# FTDI-Breakout_v20.net
KiCad netlist of a schematic drawn in EAGLE
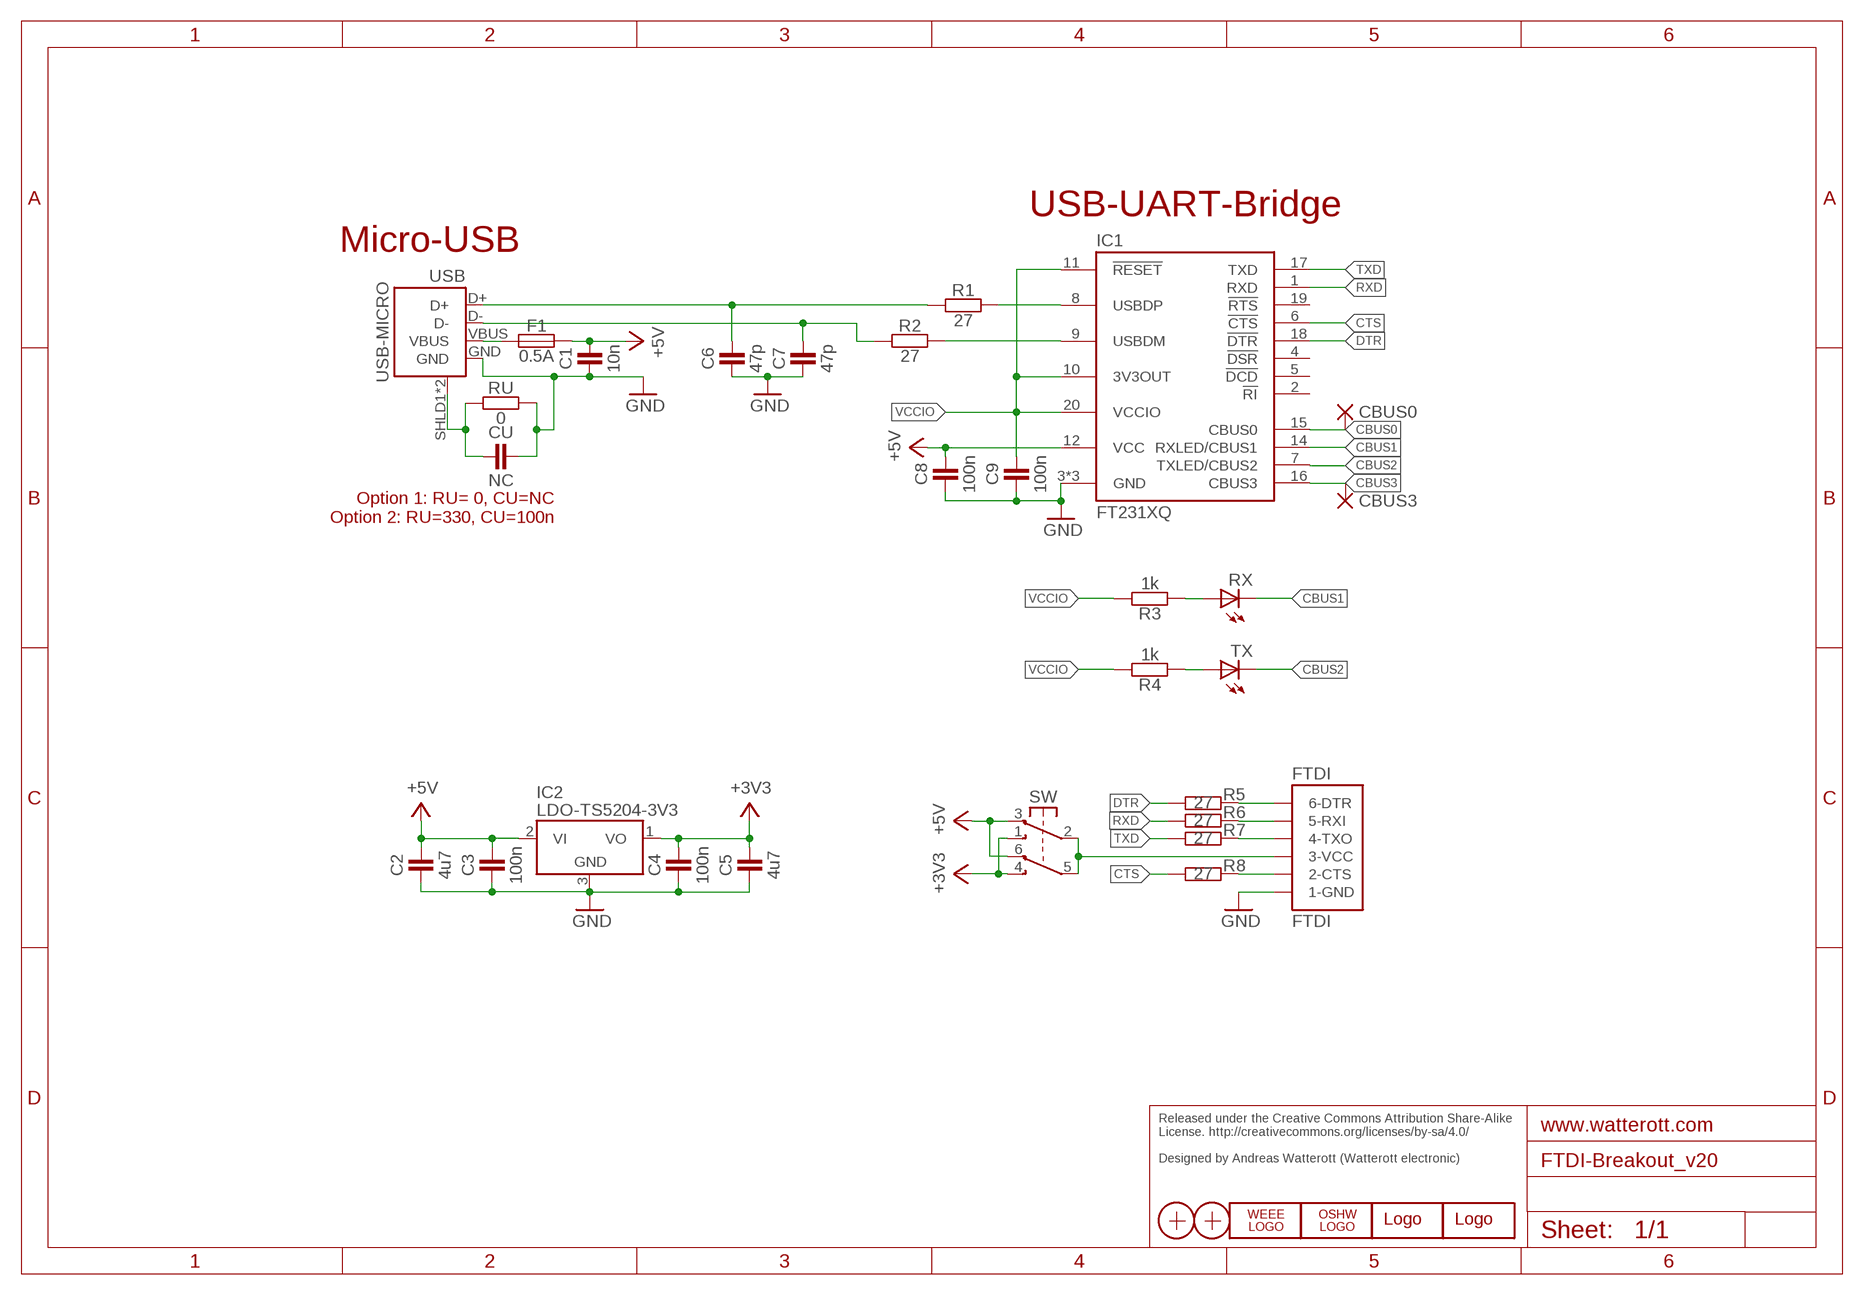
[diagram p0: schematic, sheet 1]

(export (version "E")
  (design (tool "Eeschema 10.0.6"))
  (components
    (comp (ref "C1")
      (value "10n")
      (footprint "eagle-import:C0603")
      (libsource (lib "eagle-import") (part "CAPACITOR-0603"))
    )
    (comp (ref "C2")
      (value "4u7")
      (footprint "eagle-import:C0805")
      (libsource (lib "eagle-import") (part "CAPACITOR-0805"))
    )
    (comp (ref "C3")
      (value "100n")
      (footprint "eagle-import:C0603")
      (libsource (lib "eagle-import") (part "CAPACITOR-0603"))
    )
    (comp (ref "C4")
      (value "100n")
      (footprint "eagle-import:C0603")
      (libsource (lib "eagle-import") (part "CAPACITOR-0603"))
    )
    (comp (ref "C5")
      (value "4u7")
      (footprint "eagle-import:C0805")
      (libsource (lib "eagle-import") (part "CAPACITOR-0805"))
    )
    (comp (ref "C6")
      (value "47p")
      (footprint "eagle-import:C0603")
      (libsource (lib "eagle-import") (part "CAPACITOR-0603"))
    )
    (comp (ref "C7")
      (value "47p")
      (footprint "eagle-import:C0603")
      (libsource (lib "eagle-import") (part "CAPACITOR-0603"))
    )
    (comp (ref "C8")
      (value "100n")
      (footprint "eagle-import:C0603")
      (libsource (lib "eagle-import") (part "CAPACITOR-0603"))
    )
    (comp (ref "C9")
      (value "100n")
      (footprint "eagle-import:C0603")
      (libsource (lib "eagle-import") (part "CAPACITOR-0603"))
    )
    (comp (ref "CBUS0")
      (value "PAD-1.27X1.27_NC")
      (footprint "eagle-import:PAD-1.27X1.27_NC")
      (libsource (lib "eagle-import") (part "PAD-1.27X1.27_NC"))
    )
    (comp (ref "CBUS3")
      (value "PAD-1.27X1.27_NC")
      (footprint "eagle-import:PAD-1.27X1.27_NC")
      (libsource (lib "eagle-import") (part "PAD-1.27X1.27_NC"))
    )
    (comp (ref "CU")
      (value "NC")
      (footprint "eagle-import:C0603")
      (libsource (lib "eagle-import") (part "CAPACITOR-0603"))
    )
    (comp (ref "F1")
      (value "0.5A")
      (footprint "eagle-import:C0805")
      (libsource (lib "eagle-import") (part "FUSE-0805"))
    )
    (comp (ref "FTDI")
      (value "FTDI")
      (footprint "eagle-import:FTDI")
      (libsource (lib "eagle-import") (part "FTDI"))
    )
    (comp (ref "IC1")
      (value "FT231XQ")
      (footprint "eagle-import:QFN20-PAD")
      (libsource (lib "eagle-import") (part "FT231XQ"))
    )
    (comp (ref "IC2")
      (value "LDO-TS5204-3V3")
      (footprint "eagle-import:SOT23")
      (libsource (lib "eagle-import") (part "LDO-TS5204-3V3"))
    )
    (comp (ref "LOGO1")
      (value "WEEE_LOGO-S")
      (footprint "eagle-import:WEEE_TPLAC_S")
      (libsource (lib "eagle-import") (part "WEEE_LOGO-S"))
    )
    (comp (ref "LOGO2")
      (value "OSHW_LOGOX0070")
      (footprint "eagle-import:OSHW_6X70")
      (libsource (lib "eagle-import") (part "OSHW_LOGOX0070"))
    )
    (comp (ref "LOGO3")
      (value "LOGO-S_PLACE_S")
      (footprint "eagle-import:SPARK_TPLACE_S")
      (libsource (lib "eagle-import") (part "LOGO-S_PLACE_S"))
    )
    (comp (ref "LOGO4")
      (value "LOGO-S_PLACE_M")
      (footprint "eagle-import:SPARK_TPLACE_M")
      (libsource (lib "eagle-import") (part "LOGO-S_PLACE_M"))
    )
    (comp (ref "R1")
      (value "27")
      (footprint "eagle-import:C0603")
      (libsource (lib "eagle-import") (part "RESISTOR-0603"))
    )
    (comp (ref "R2")
      (value "27")
      (footprint "eagle-import:C0603")
      (libsource (lib "eagle-import") (part "RESISTOR-0603"))
    )
    (comp (ref "R3")
      (value "1k")
      (footprint "eagle-import:C0603")
      (libsource (lib "eagle-import") (part "RESISTOR-0603"))
    )
    (comp (ref "R4")
      (value "1k")
      (footprint "eagle-import:C0603")
      (libsource (lib "eagle-import") (part "RESISTOR-0603"))
    )
    (comp (ref "R5")
      (value "27")
      (footprint "eagle-import:C0603")
      (libsource (lib "eagle-import") (part "RESISTOR-0603"))
    )
    (comp (ref "R6")
      (value "27")
      (footprint "eagle-import:C0603")
      (libsource (lib "eagle-import") (part "RESISTOR-0603"))
    )
    (comp (ref "R7")
      (value "27")
      (footprint "eagle-import:C0603")
      (libsource (lib "eagle-import") (part "RESISTOR-0603"))
    )
    (comp (ref "R8")
      (value "27")
      (footprint "eagle-import:C0603")
      (libsource (lib "eagle-import") (part "RESISTOR-0603"))
    )
    (comp (ref "RU")
      (value "0")
      (footprint "eagle-import:C0603")
      (libsource (lib "eagle-import") (part "RESISTOR-0603"))
    )
    (comp (ref "RX")
      (value "LED-0603")
      (footprint "eagle-import:C0603")
      (libsource (lib "eagle-import") (part "LED-0603"))
    )
    (comp (ref "SW")
      (value "SW-2UM-CUS22B")
      (footprint "eagle-import:SW_CUS22B")
      (libsource (lib "eagle-import") (part "SW-2UM-CUS22B"))
    )
    (comp (ref "TX")
      (value "LED-0603")
      (footprint "eagle-import:C0603")
      (libsource (lib "eagle-import") (part "LED-0603"))
    )
    (comp (ref "USB")
      (value "USB-MICRO")
      (footprint "eagle-import:USB-MICRO-10103594")
      (libsource (lib "eagle-import") (part "USB-MICRO"))
    )
    (comp (ref "X1")
      (value "PASSER-07")
      (footprint "eagle-import:PASSER_07MM")
      (libsource (lib "eagle-import") (part "PASSER-07"))
    )
    (comp (ref "X2")
      (value "PASSER-07")
      (footprint "eagle-import:PASSER_07MM")
      (libsource (lib "eagle-import") (part "PASSER-07"))
    )
  )
  (nets
    (net (code "1") (name "+3V3") (class "Default")
      (node (ref "C4") (pin "2") (pinfunction "2_2") (pintype "passive"))
      (node (ref "C5") (pin "2") (pinfunction "2_2") (pintype "passive"))
      (node (ref "IC2") (pin "1") (pinfunction "VO_1") (pintype "passive"))
      (node (ref "SW") (pin "1") (pinfunction "S1_1") (pintype "passive"))
      (node (ref "SW") (pin "4") (pinfunction "S2_4") (pintype "passive"))
    )
    (net (code "2") (name "+5V") (class "Default")
      (node (ref "C1") (pin "2") (pinfunction "2_2") (pintype "passive"))
      (node (ref "C2") (pin "2") (pinfunction "2_2") (pintype "passive"))
      (node (ref "C3") (pin "2") (pinfunction "2_2") (pintype "passive"))
      (node (ref "C8") (pin "2") (pinfunction "2_2") (pintype "passive"))
      (node (ref "F1") (pin "2") (pinfunction "2_2") (pintype "passive"))
      (node (ref "IC1") (pin "12") (pinfunction "VCC_12") (pintype "power_in"))
      (node (ref "IC2") (pin "2") (pinfunction "VI_2") (pintype "input"))
      (node (ref "SW") (pin "3") (pinfunction "O1_3") (pintype "passive"))
      (node (ref "SW") (pin "6") (pinfunction "O2_6") (pintype "passive"))
    )
    (net (code "3") (name "CBUS0") (class "Default")
      (node (ref "CBUS0") (pin "1") (pinfunction "P_1") (pintype "passive"))
      (node (ref "IC1") (pin "15") (pinfunction "CBUS0_15") (pintype "bidirectional"))
    )
    (net (code "4") (name "CBUS1") (class "Default")
      (node (ref "IC1") (pin "14") (pinfunction "RXLED/CBUS1_14") (pintype "bidirectional"))
      (node (ref "RX") (pin "C") (pinfunction "C_C") (pintype "passive"))
    )
    (net (code "5") (name "CBUS2") (class "Default")
      (node (ref "IC1") (pin "7") (pinfunction "TXLED/CBUS2_7") (pintype "bidirectional"))
      (node (ref "TX") (pin "C") (pinfunction "C_C") (pintype "passive"))
    )
    (net (code "6") (name "CBUS3") (class "Default")
      (node (ref "CBUS3") (pin "1") (pinfunction "P_1") (pintype "passive"))
      (node (ref "IC1") (pin "16") (pinfunction "CBUS3_16") (pintype "bidirectional"))
    )
    (net (code "7") (name "CTS") (class "Default")
      (node (ref "IC1") (pin "6") (pinfunction "~{CTS}_6") (pintype "bidirectional"))
      (node (ref "R8") (pin "1") (pinfunction "1_1") (pintype "passive"))
    )
    (net (code "8") (name "DTR") (class "Default")
      (node (ref "IC1") (pin "18") (pinfunction "~{DTR}_18") (pintype "bidirectional"))
      (node (ref "R5") (pin "1") (pinfunction "1_1") (pintype "passive"))
    )
    (net (code "9") (name "GND") (class "Default")
      (node (ref "C1") (pin "1") (pinfunction "1_1") (pintype "passive"))
      (node (ref "C2") (pin "1") (pinfunction "1_1") (pintype "passive"))
      (node (ref "C3") (pin "1") (pinfunction "1_1") (pintype "passive"))
      (node (ref "C4") (pin "1") (pinfunction "1_1") (pintype "passive"))
      (node (ref "C5") (pin "1") (pinfunction "1_1") (pintype "passive"))
      (node (ref "C6") (pin "1") (pinfunction "1_1") (pintype "passive"))
      (node (ref "C7") (pin "1") (pinfunction "1_1") (pintype "passive"))
      (node (ref "C8") (pin "1") (pinfunction "1_1") (pintype "passive"))
      (node (ref "C9") (pin "1") (pinfunction "1_1") (pintype "passive"))
      (node (ref "CU") (pin "2") (pinfunction "2_2") (pintype "passive"))
      (node (ref "FTDI") (pin "1-GND") (pinfunction "1-GND_1-GND") (pintype "power_in"))
      (node (ref "IC1") (pin "13") (pinfunction "GND_13") (pintype "power_in"))
      (node (ref "IC1") (pin "3") (pinfunction "GND_3") (pintype "power_in"))
      (node (ref "IC1") (pin "TP") (pinfunction "GND_TP") (pintype "power_in"))
      (node (ref "IC2") (pin "3") (pinfunction "GND_3") (pintype "passive"))
      (node (ref "RU") (pin "2") (pinfunction "2_2") (pintype "passive"))
      (node (ref "USB") (pin "GND") (pinfunction "GND_GND") (pintype "power_in"))
    )
    (net (code "10") (name "Net-(C6-Pad2)") (class "Default")
      (node (ref "C6") (pin "2") (pinfunction "2_2") (pintype "passive"))
      (node (ref "R1") (pin "1") (pinfunction "1_1") (pintype "passive"))
      (node (ref "USB") (pin "D+") (pinfunction "D+_D+") (pintype "bidirectional"))
    )
    (net (code "11") (name "Net-(C7-Pad2)") (class "Default")
      (node (ref "C7") (pin "2") (pinfunction "2_2") (pintype "passive"))
      (node (ref "R2") (pin "1") (pinfunction "1_1") (pintype "passive"))
      (node (ref "USB") (pin "D-") (pinfunction "D-_D-") (pintype "bidirectional"))
    )
    (net (code "12") (name "Net-(CU-Pad1)") (class "Default")
      (node (ref "CU") (pin "1") (pinfunction "1_1") (pintype "passive"))
      (node (ref "RU") (pin "1") (pinfunction "1_1") (pintype "passive"))
      (node (ref "USB") (pin "SHLD1") (pinfunction "SHIELD_SHLD1") (pintype "passive"))
      (node (ref "USB") (pin "SHLD2") (pinfunction "SHIELD_SHLD2") (pintype "passive"))
    )
    (net (code "13") (name "Net-(F1-Pad1)") (class "Default")
      (node (ref "F1") (pin "1") (pinfunction "1_1") (pintype "passive"))
      (node (ref "USB") (pin "VBUS") (pinfunction "VBUS_VBUS") (pintype "power_in"))
    )
    (net (code "14") (name "Net-(FTDI-4-TXO)") (class "Default")
      (node (ref "FTDI") (pin "4-TX") (pinfunction "4-TXO_4-TX") (pintype "bidirectional"))
      (node (ref "R7") (pin "2") (pinfunction "2_2") (pintype "passive"))
    )
    (net (code "15") (name "Net-(FTDI-5-RXI)") (class "Default")
      (node (ref "FTDI") (pin "5-RX") (pinfunction "5-RXI_5-RX") (pintype "bidirectional"))
      (node (ref "R6") (pin "2") (pinfunction "2_2") (pintype "passive"))
    )
    (net (code "16") (name "Net-(FTDI-Pad2-CTS)") (class "Default")
      (node (ref "FTDI") (pin "2-CTS") (pinfunction "2-CTS_2-CTS") (pintype "bidirectional"))
      (node (ref "R8") (pin "2") (pinfunction "2_2") (pintype "passive"))
    )
    (net (code "17") (name "Net-(FTDI-Pad6-DTR)") (class "Default")
      (node (ref "FTDI") (pin "6-DTR") (pinfunction "6-DTR_6-DTR") (pintype "bidirectional"))
      (node (ref "R5") (pin "2") (pinfunction "2_2") (pintype "passive"))
    )
    (net (code "18") (name "Net-(IC1-USBDM)") (class "Default")
      (node (ref "IC1") (pin "9") (pinfunction "USBDM_9") (pintype "bidirectional"))
      (node (ref "R2") (pin "2") (pinfunction "2_2") (pintype "passive"))
    )
    (net (code "19") (name "Net-(IC1-USBDP)") (class "Default")
      (node (ref "IC1") (pin "8") (pinfunction "USBDP_8") (pintype "bidirectional"))
      (node (ref "R1") (pin "2") (pinfunction "2_2") (pintype "passive"))
    )
    (net (code "20") (name "Net-(R3-Pad1)") (class "Default")
      (node (ref "R3") (pin "1") (pinfunction "1_1") (pintype "passive"))
      (node (ref "RX") (pin "A") (pinfunction "A_A") (pintype "passive"))
    )
    (net (code "21") (name "Net-(R4-Pad1)") (class "Default")
      (node (ref "R4") (pin "1") (pinfunction "1_1") (pintype "passive"))
      (node (ref "TX") (pin "A") (pinfunction "A_A") (pintype "passive"))
    )
    (net (code "22") (name "Net-(SW-P1)") (class "Default")
      (node (ref "FTDI") (pin "3-VCC") (pinfunction "3-VCC_3-VCC") (pintype "power_in"))
      (node (ref "SW") (pin "2") (pinfunction "P1_2") (pintype "passive"))
      (node (ref "SW") (pin "5") (pinfunction "P2_5") (pintype "passive"))
    )
    (net (code "23") (name "RXD") (class "Default")
      (node (ref "IC1") (pin "1") (pinfunction "RXD_1") (pintype "bidirectional"))
      (node (ref "R6") (pin "1") (pinfunction "1_1") (pintype "passive"))
    )
    (net (code "24") (name "TXD") (class "Default")
      (node (ref "IC1") (pin "17") (pinfunction "TXD_17") (pintype "bidirectional"))
      (node (ref "R7") (pin "1") (pinfunction "1_1") (pintype "passive"))
    )
    (net (code "25") (name "VCCIO") (class "Default")
      (node (ref "C9") (pin "2") (pinfunction "2_2") (pintype "passive"))
      (node (ref "IC1") (pin "10") (pinfunction "3V3OUT_10") (pintype "power_in"))
      (node (ref "IC1") (pin "11") (pinfunction "~{RESET}_11") (pintype "bidirectional"))
      (node (ref "IC1") (pin "20") (pinfunction "VCCIO_20") (pintype "power_in"))
      (node (ref "R3") (pin "2") (pinfunction "2_2") (pintype "passive"))
      (node (ref "R4") (pin "2") (pinfunction "2_2") (pintype "passive"))
    )
    (net (code "26") (name "unconnected-(IC1-~{DCD}-Pad5)") (class "Default")
      (node (ref "IC1") (pin "5") (pinfunction "~{DCD}_5") (pintype "bidirectional"))
    )
    (net (code "27") (name "unconnected-(IC1-~{DSR}-Pad4)") (class "Default")
      (node (ref "IC1") (pin "4") (pinfunction "~{DSR}_4") (pintype "bidirectional"))
    )
    (net (code "28") (name "unconnected-(IC1-~{RI}-Pad2)") (class "Default")
      (node (ref "IC1") (pin "2") (pinfunction "~{RI}_2") (pintype "bidirectional"))
    )
    (net (code "29") (name "unconnected-(IC1-~{RTS}-Pad19)") (class "Default")
      (node (ref "IC1") (pin "19") (pinfunction "~{RTS}_19") (pintype "bidirectional"))
    )
  )
)
